# Encoder_Sheet.net
KiCad netlist of a schematic drawn in Altium Designer
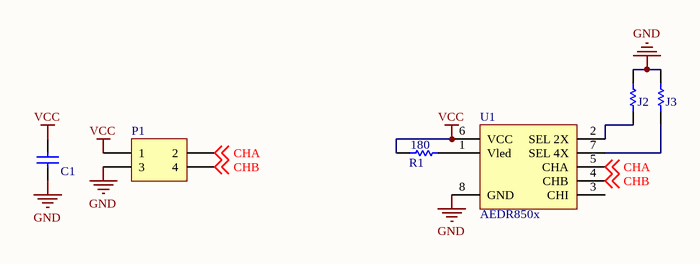
[diagram p0: Encoder_Sheet.SchDoc]

(export (version "E")
  (design (tool "Eeschema 10.0.6"))
  (components
    (comp (ref "C1")
      (value "?F")
      (footprint "1608[0603]")
      (description "Capacitor")
      (libsource (lib "AlmaLib1") (part "Cap_BP"))
    )
    (comp (ref "J2")
      (value "*")
      (footprint "1005[0402]")
      (description "Res")
      (libsource (lib "AlmaLib1") (part "Res"))
    )
    (comp (ref "J3")
      (value "*")
      (footprint "1005[0402]")
      (description "Res")
      (libsource (lib "AlmaLib1") (part "Res"))
    )
    (comp (ref "P1")
      (value "Header 2X2")
      (footprint "HDR2X2")
      (description "Header, 2-Pin, Dual row")
      (fields (field (name "PUBLISHER") "Altium Limited"))
      (libsource (lib "Miscellaneous Connectors") (part "Header 2X2"))
    )
    (comp (ref "R1")
      (value "180")
      (footprint "1608[0603]")
      (description "Res")
      (libsource (lib "AlmaLib1") (part "Res"))
    )
    (comp (ref "U1")
      (value "AEDR850x")
      (footprint "AEDR-850x")
      (description "Reflectiveo Optical Encoder")
      (libsource (lib "AlmaLib1") (part "AEDR850x"))
    )
  )
  (nets
    (net (code "1") (name "CHA") (class "Default")
      (node (ref "P1") (pin "2") (pinfunction "2_2") (pintype "passive"))
      (node (ref "U1") (pin "5") (pinfunction "CHA_5") (pintype "passive"))
    )
    (net (code "2") (name "CHB") (class "Default")
      (node (ref "P1") (pin "4") (pinfunction "4_4") (pintype "passive"))
      (node (ref "U1") (pin "4") (pinfunction "CHB_4") (pintype "passive"))
    )
    (net (code "3") (name "GND") (class "Default")
      (node (ref "C1") (pin "1") (pinfunction "1_1") (pintype "passive"))
      (node (ref "J2") (pin "2") (pinfunction "2_2") (pintype "passive"))
      (node (ref "J3") (pin "2") (pinfunction "2_2") (pintype "passive"))
      (node (ref "P1") (pin "3") (pinfunction "3_3") (pintype "passive"))
      (node (ref "U1") (pin "8") (pinfunction "GND_8") (pintype "passive"))
    )
    (net (code "4") (name "Net-(U1-SEL_2X)") (class "Default")
      (node (ref "J2") (pin "1") (pinfunction "1_1") (pintype "passive"))
      (node (ref "U1") (pin "2") (pinfunction "SEL_2X_2") (pintype "passive"))
    )
    (net (code "5") (name "Net-(U1-SEL_4X)") (class "Default")
      (node (ref "J3") (pin "1") (pinfunction "1_1") (pintype "passive"))
      (node (ref "U1") (pin "7") (pinfunction "SEL_4X_7") (pintype "passive"))
    )
    (net (code "6") (name "Net-(U1-Vled)") (class "Default")
      (node (ref "R1") (pin "2") (pinfunction "2_2") (pintype "passive"))
      (node (ref "U1") (pin "1") (pinfunction "Vled_1") (pintype "power_in"))
    )
    (net (code "7") (name "VCC") (class "Default")
      (node (ref "C1") (pin "2") (pinfunction "2_2") (pintype "passive"))
      (node (ref "P1") (pin "1") (pinfunction "1_1") (pintype "passive"))
      (node (ref "R1") (pin "1") (pinfunction "1_1") (pintype "passive"))
      (node (ref "U1") (pin "6") (pinfunction "VCC_6") (pintype "power_in"))
    )
    (net (code "8") (name "unconnected-(U1-CHI-Pad3)") (class "Default")
      (node (ref "U1") (pin "3") (pinfunction "CHI_3") (pintype "passive"))
    )
  )
)
